# daGloane1_1.net
KiCad netlist of a schematic drawn in EAGLE
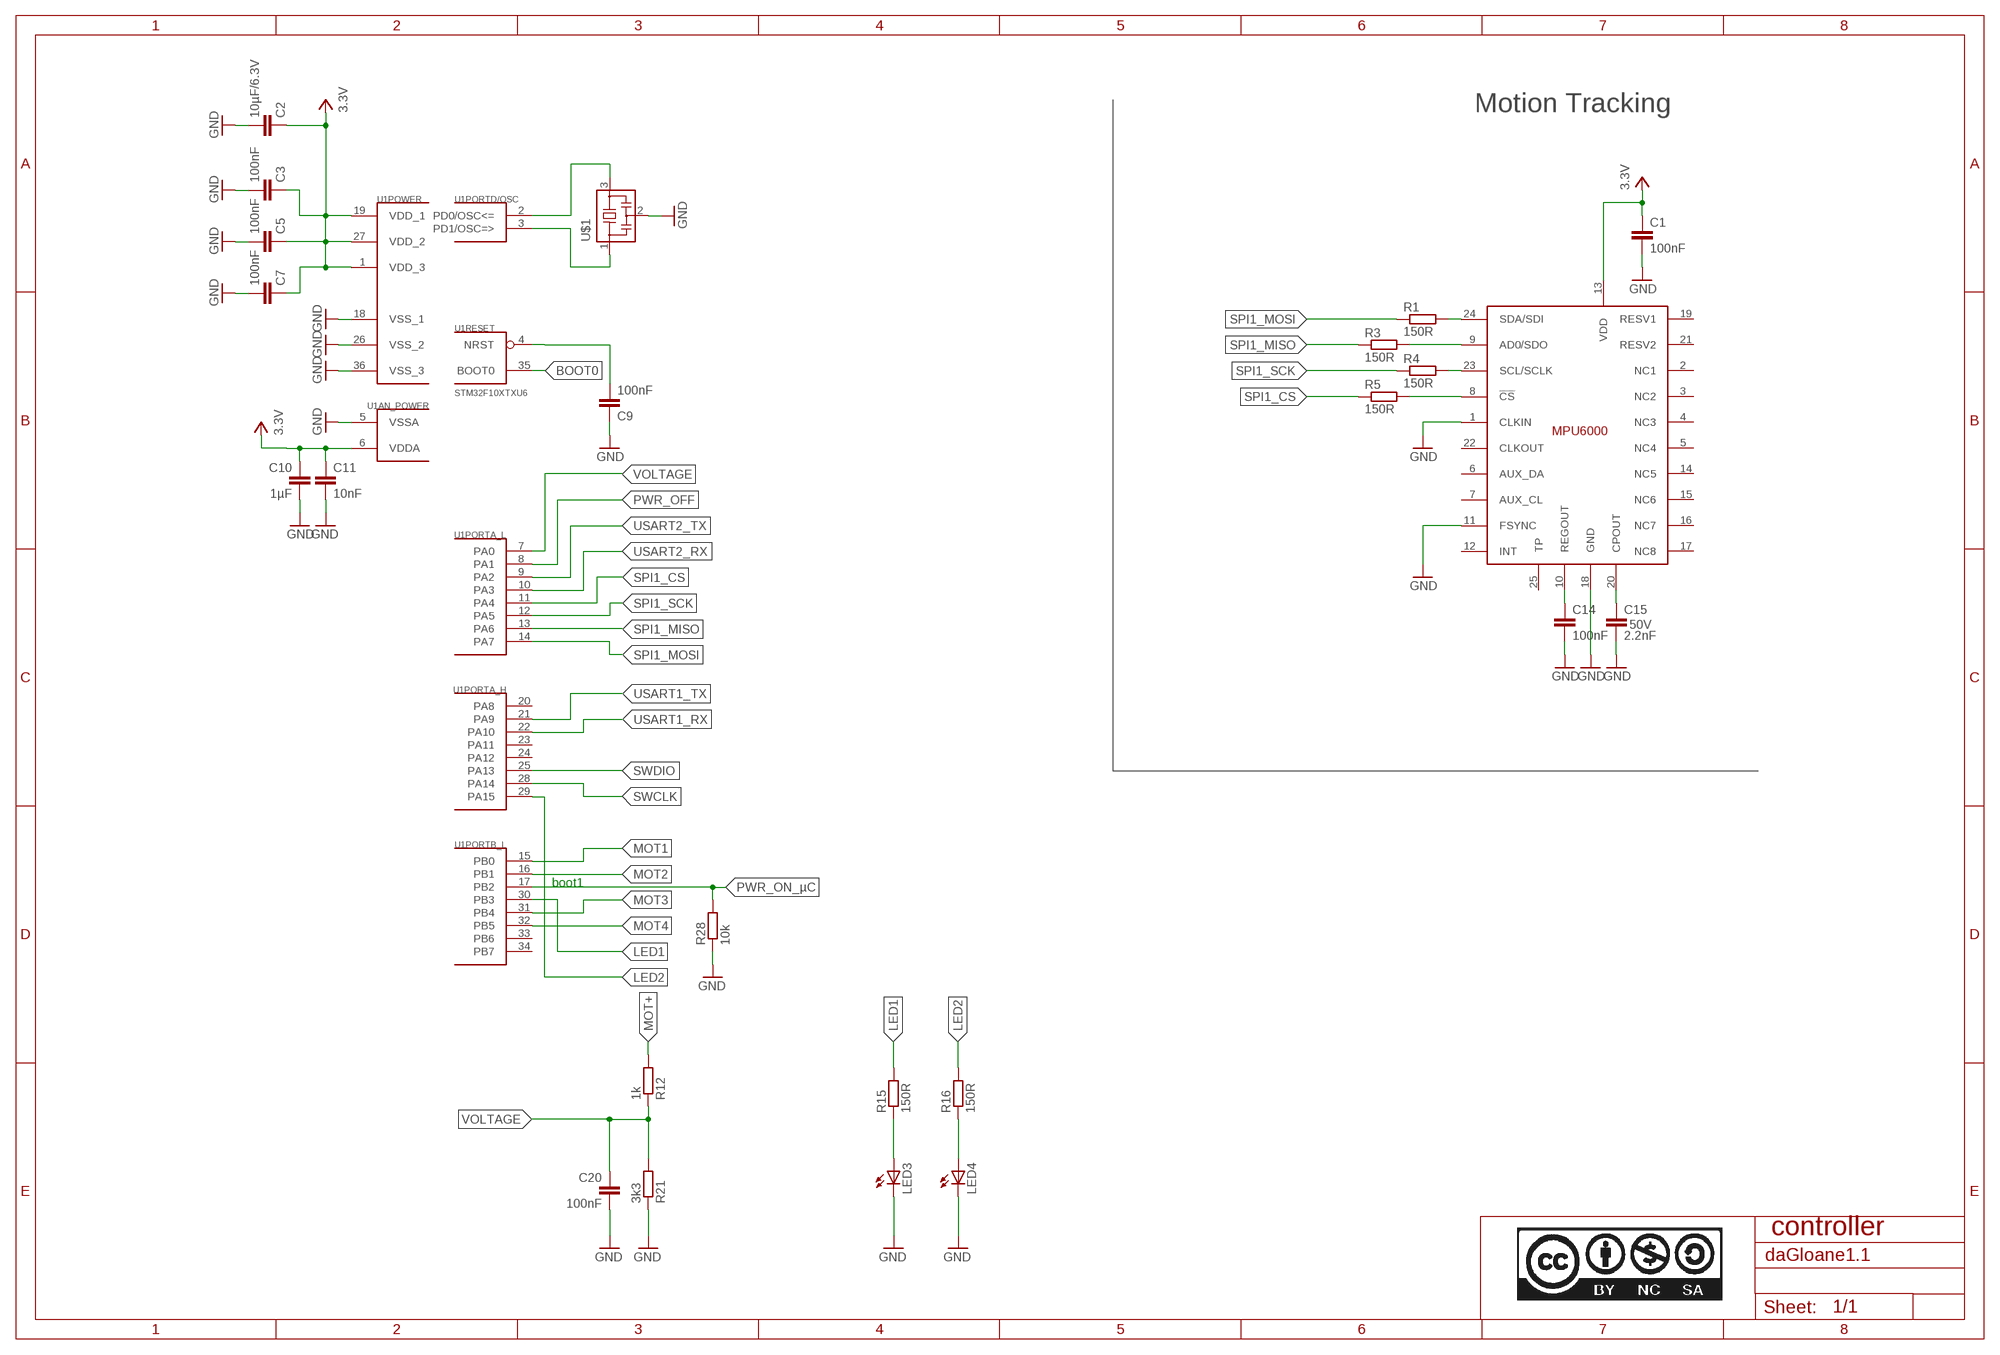
[diagram p0: schematic, sheet 1, part 1 of 3]
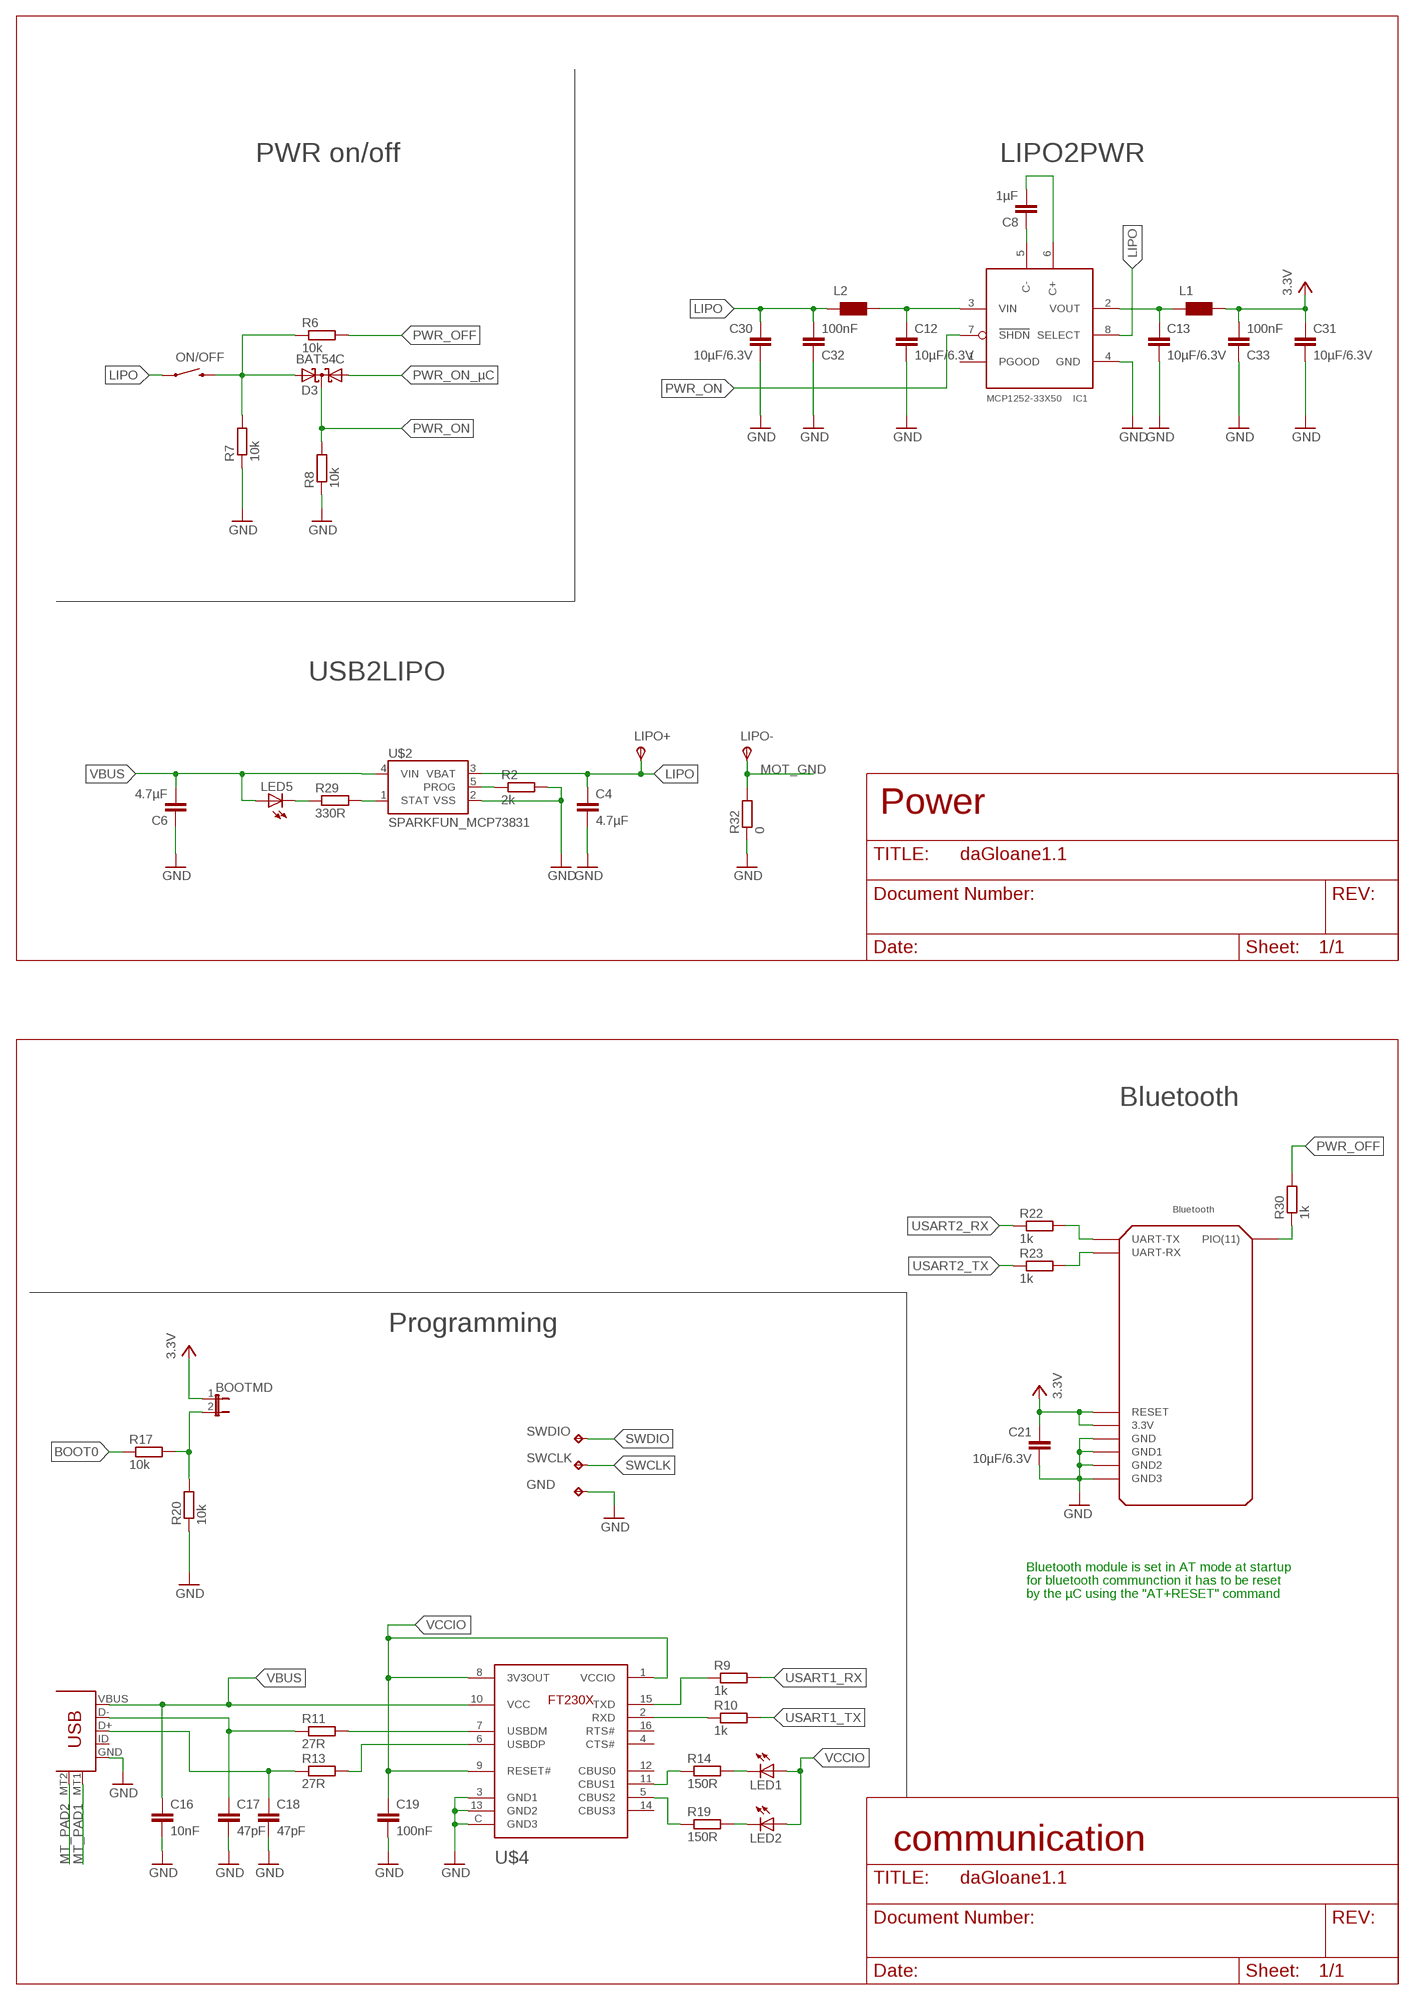
[diagram p1: schematic, sheet 1, part 2 of 3]
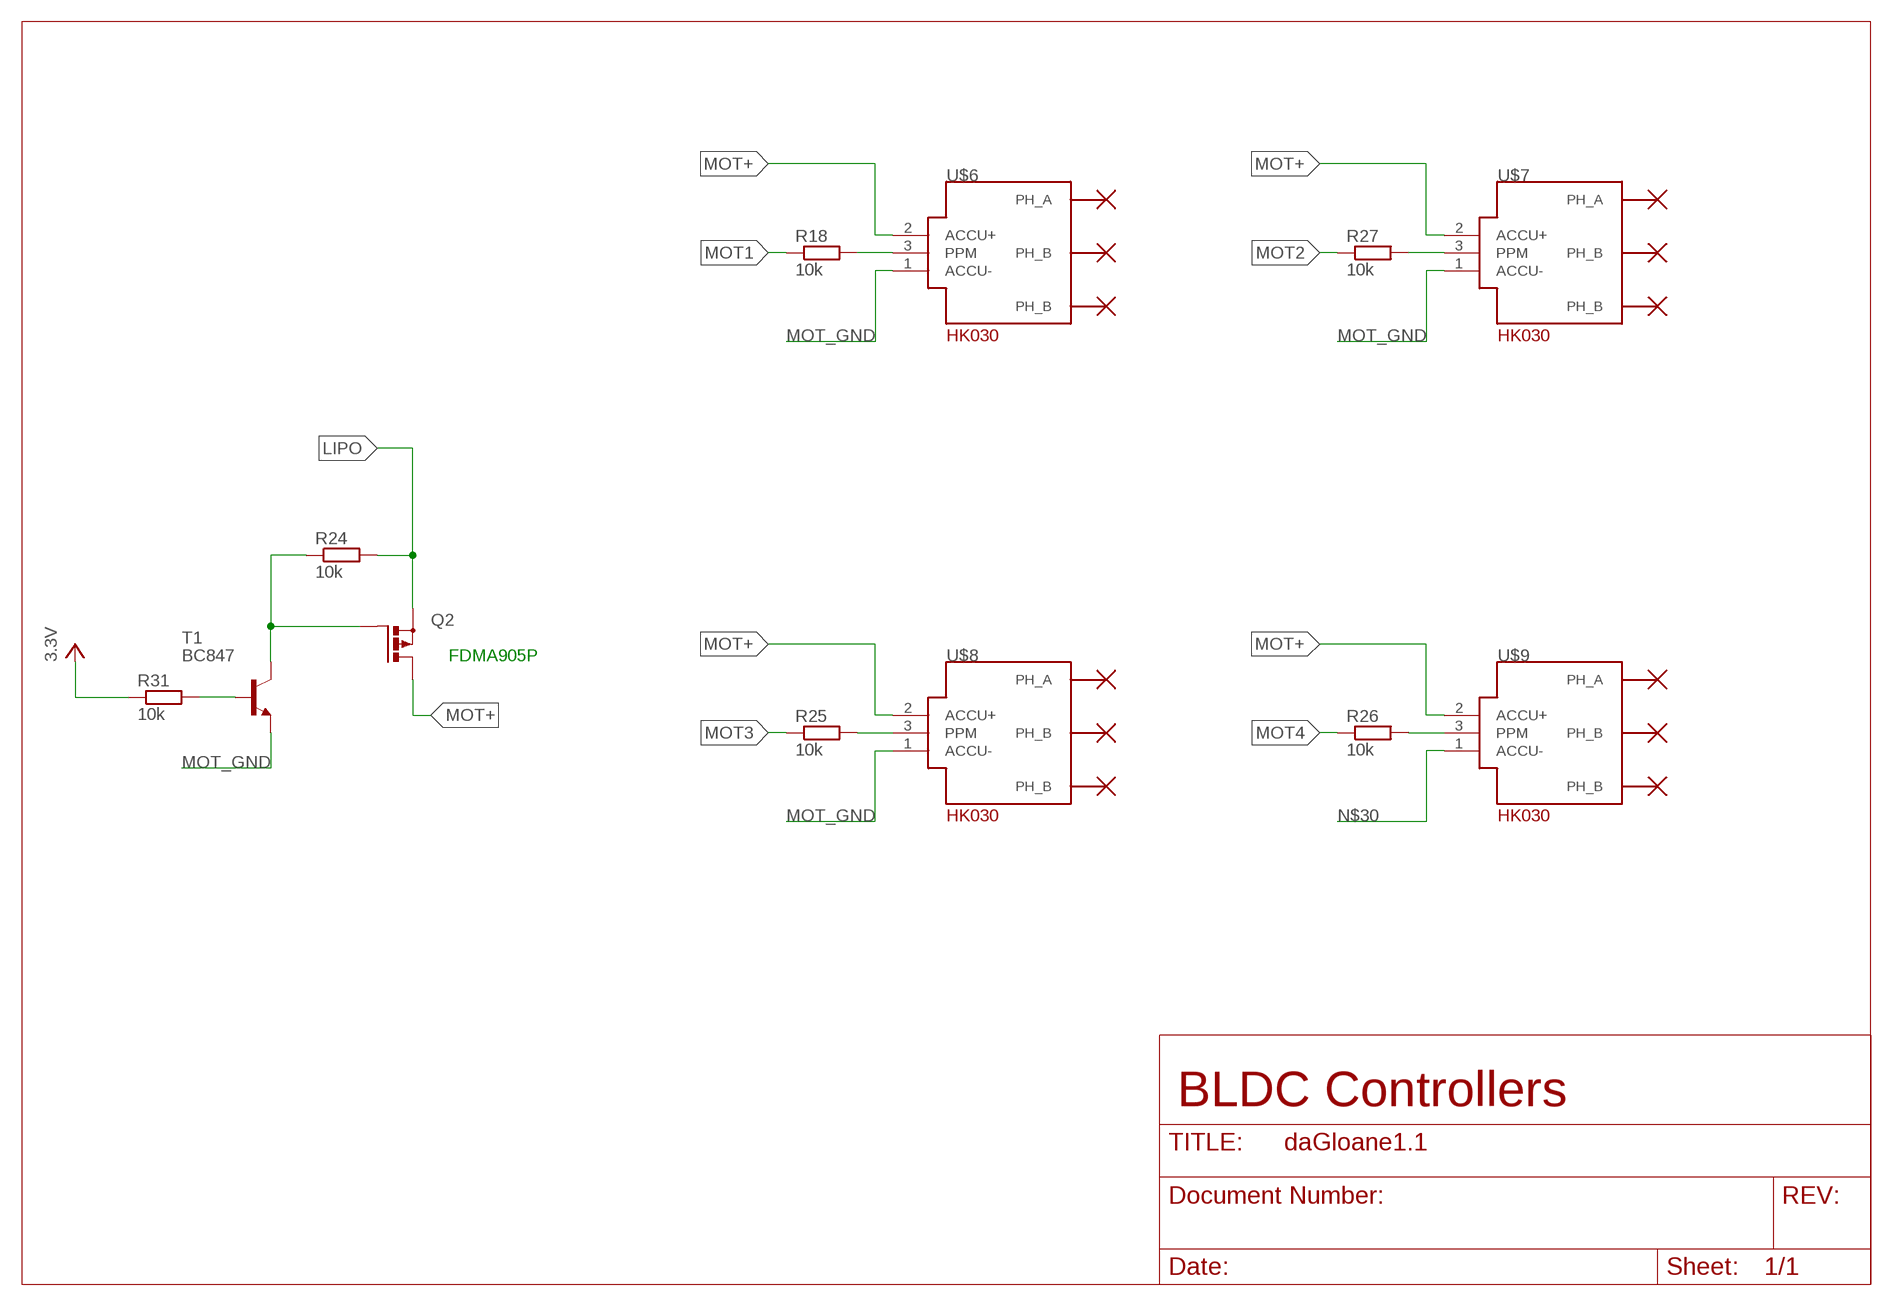
[diagram p2: schematic, sheet 1, part 3 of 3]

(export (version "E")
  (design (tool "Eeschema 10.0.6"))
  (components
    (comp (ref "BOOTMD")
      (value "JUMPER-2")
      (footprint "eagle-import:1X02_50MIL")
      (libsource (lib "eagle-import") (part "JUMPER-2"))
    )
    (comp (ref "C1")
      (value "100nF")
      (footprint "eagle-import:C0603")
      (libsource (lib "eagle-import") (part "C-EUC0603"))
    )
    (comp (ref "C2")
      (value "10µF/6.3V")
      (footprint "eagle-import:C0805")
      (libsource (lib "eagle-import") (part "C-EUC0805"))
    )
    (comp (ref "C3")
      (value "100nF")
      (footprint "eagle-import:C0603")
      (libsource (lib "eagle-import") (part "C-EUC0603"))
    )
    (comp (ref "C4")
      (value "4.7µF")
      (footprint "eagle-import:C0603")
      (libsource (lib "eagle-import") (part "C-EUC0603"))
    )
    (comp (ref "C5")
      (value "100nF")
      (footprint "eagle-import:C0603")
      (libsource (lib "eagle-import") (part "C-EUC0603"))
    )
    (comp (ref "C6")
      (value "4.7µF")
      (footprint "eagle-import:C0603")
      (libsource (lib "eagle-import") (part "C-EUC0603"))
    )
    (comp (ref "C7")
      (value "100nF")
      (footprint "eagle-import:C0603")
      (libsource (lib "eagle-import") (part "C-EUC0603"))
    )
    (comp (ref "C8")
      (value "1µF")
      (footprint "eagle-import:C0603")
      (libsource (lib "eagle-import") (part "C-EUC0603"))
    )
    (comp (ref "C9")
      (value "100nF")
      (footprint "eagle-import:C0603")
      (libsource (lib "eagle-import") (part "C-EUC0603"))
    )
    (comp (ref "C10")
      (value "1µF")
      (footprint "eagle-import:C0603")
      (libsource (lib "eagle-import") (part "C-EUC0603"))
    )
    (comp (ref "C11")
      (value "10nF")
      (footprint "eagle-import:C0603")
      (libsource (lib "eagle-import") (part "C-EUC0603"))
    )
    (comp (ref "C12")
      (value "10µF/6.3V")
      (footprint "eagle-import:C0805")
      (libsource (lib "eagle-import") (part "C-EUC0805"))
    )
    (comp (ref "C13")
      (value "10µF/6.3V")
      (footprint "eagle-import:C0805")
      (libsource (lib "eagle-import") (part "C-EUC0805"))
    )
    (comp (ref "C14")
      (value "100nF")
      (footprint "eagle-import:C0603")
      (libsource (lib "eagle-import") (part "C-EUC0603"))
    )
    (comp (ref "C15")
      (value "2.2nF")
      (footprint "eagle-import:C0603")
      (fields (field (name "VOLTAGE") "50V"))
      (libsource (lib "eagle-import") (part "C-EUC0603"))
    )
    (comp (ref "C16")
      (value "10nF")
      (footprint "eagle-import:C0603")
      (libsource (lib "eagle-import") (part "C-EUC0603"))
    )
    (comp (ref "C17")
      (value "47pF")
      (footprint "eagle-import:C0603")
      (libsource (lib "eagle-import") (part "C-EUC0603"))
    )
    (comp (ref "C18")
      (value "47pF")
      (footprint "eagle-import:C0603")
      (libsource (lib "eagle-import") (part "C-EUC0603"))
    )
    (comp (ref "C19")
      (value "100nF")
      (footprint "eagle-import:C0603")
      (libsource (lib "eagle-import") (part "C-EUC0603"))
    )
    (comp (ref "C20")
      (value "100nF")
      (footprint "eagle-import:C0603")
      (libsource (lib "eagle-import") (part "C-EUC0603"))
    )
    (comp (ref "C21")
      (value "10µF/6.3V")
      (footprint "eagle-import:C0805")
      (libsource (lib "eagle-import") (part "C-EUC0805"))
    )
    (comp (ref "C30")
      (value "10µF/6.3V")
      (footprint "eagle-import:C0805")
      (libsource (lib "eagle-import") (part "C-EUC0805"))
    )
    (comp (ref "C31")
      (value "10µF/6.3V")
      (footprint "eagle-import:C0805")
      (libsource (lib "eagle-import") (part "C-EUC0805"))
    )
    (comp (ref "C32")
      (value "100nF")
      (footprint "eagle-import:C0603")
      (libsource (lib "eagle-import") (part "C-EUC0603"))
    )
    (comp (ref "C33")
      (value "100nF")
      (footprint "eagle-import:C0603")
      (libsource (lib "eagle-import") (part "C-EUC0603"))
    )
    (comp (ref "D3")
      (value "BAT54C")
      (footprint "eagle-import:SOT23")
      (libsource (lib "eagle-import") (part "BAT54C"))
    )
    (comp (ref "GND")
      (value "TESTPAD_TPB1,27")
      (footprint "eagle-import:TESTPAD_B1,27")
      (libsource (lib "eagle-import") (part "TESTPAD_TPB1,27"))
    )
    (comp (ref "IC1")
      (value "MCP1252-33X50")
      (footprint "eagle-import:MSOP8")
      (libsource (lib "eagle-import") (part "MCP1252-33X50"))
    )
    (comp (ref "L1")
      (value "WUERTH-ELEKTRONIK_WE-KI_0805_B")
      (footprint "eagle-import:WUERTH-ELEKTRONIK_WE-KI_0805_B")
      (libsource (lib "eagle-import") (part "WUERTH-ELEKTRONIK_WE-KI_0805_B"))
    )
    (comp (ref "L2")
      (value "WUERTH-ELEKTRONIK_WE-KI_0805_B")
      (footprint "eagle-import:WUERTH-ELEKTRONIK_WE-KI_0805_B")
      (libsource (lib "eagle-import") (part "WUERTH-ELEKTRONIK_WE-KI_0805_B"))
    )
    (comp (ref "LED1")
      (value "LEDCHIPLED_0603")
      (footprint "eagle-import:CHIPLED_0603")
      (libsource (lib "eagle-import") (part "LEDCHIPLED_0603"))
    )
    (comp (ref "LED2")
      (value "LEDCHIPLED_0603")
      (footprint "eagle-import:CHIPLED_0603")
      (libsource (lib "eagle-import") (part "LEDCHIPLED_0603"))
    )
    (comp (ref "LED3")
      (value "LEDCHIPLED_0603")
      (footprint "eagle-import:CHIPLED_0603")
      (libsource (lib "eagle-import") (part "LEDCHIPLED_0603"))
    )
    (comp (ref "LED4")
      (value "LEDCHIPLED_0603")
      (footprint "eagle-import:CHIPLED_0603")
      (libsource (lib "eagle-import") (part "LEDCHIPLED_0603"))
    )
    (comp (ref "LED5")
      (value "LEDCHIPLED_0603")
      (footprint "eagle-import:CHIPLED_0603")
      (libsource (lib "eagle-import") (part "LEDCHIPLED_0603"))
    )
    (comp (ref "LIPO+")
      (value "TPSPAD1-13")
      (footprint "eagle-import:P1-13")
      (libsource (lib "eagle-import") (part "TPSPAD1-13"))
    )
    (comp (ref "LIPO-")
      (value "TPSPAD1-13")
      (footprint "eagle-import:P1-13")
      (libsource (lib "eagle-import") (part "TPSPAD1-13"))
    )
    (comp (ref "ON/OFF")
      (value "SWITCH-MOMENTARY-2SMD")
      (footprint "eagle-import:TACTILE_SWITCH_SMD")
      (libsource (lib "eagle-import") (part "SWITCH-MOMENTARY-2SMD"))
    )
    (comp (ref "Q2")
      (value "P-MOSFET-SO8")
      (footprint "eagle-import:MICROFET2X2")
      (libsource (lib "eagle-import") (part "P-MOSFET-SO8"))
    )
    (comp (ref "R1")
      (value "150R")
      (footprint "eagle-import:R0603")
      (libsource (lib "eagle-import") (part "R-EU_R0603"))
    )
    (comp (ref "R2")
      (value "2k")
      (footprint "eagle-import:R0603")
      (libsource (lib "eagle-import") (part "R-EU_R0603"))
    )
    (comp (ref "R3")
      (value "150R")
      (footprint "eagle-import:R0603")
      (libsource (lib "eagle-import") (part "R-EU_R0603"))
    )
    (comp (ref "R4")
      (value "150R")
      (footprint "eagle-import:R0603")
      (libsource (lib "eagle-import") (part "R-EU_R0603"))
    )
    (comp (ref "R5")
      (value "150R")
      (footprint "eagle-import:R0603")
      (libsource (lib "eagle-import") (part "R-EU_R0603"))
    )
    (comp (ref "R6")
      (value "10k")
      (footprint "eagle-import:R0603")
      (libsource (lib "eagle-import") (part "R-EU_R0603"))
    )
    (comp (ref "R7")
      (value "10k")
      (footprint "eagle-import:R0603")
      (libsource (lib "eagle-import") (part "R-EU_R0603"))
    )
    (comp (ref "R8")
      (value "10k")
      (footprint "eagle-import:R0603")
      (libsource (lib "eagle-import") (part "R-EU_R0603"))
    )
    (comp (ref "R9")
      (value "1k")
      (footprint "eagle-import:R0603")
      (libsource (lib "eagle-import") (part "R-EU_R0603"))
    )
    (comp (ref "R10")
      (value "1k")
      (footprint "eagle-import:R0603")
      (libsource (lib "eagle-import") (part "R-EU_R0603"))
    )
    (comp (ref "R11")
      (value "27R")
      (footprint "eagle-import:R0603")
      (libsource (lib "eagle-import") (part "R-EU_R0603"))
    )
    (comp (ref "R12")
      (value "1k")
      (footprint "eagle-import:R0603")
      (libsource (lib "eagle-import") (part "R-EU_R0603"))
    )
    (comp (ref "R13")
      (value "27R")
      (footprint "eagle-import:R0603")
      (libsource (lib "eagle-import") (part "R-EU_R0603"))
    )
    (comp (ref "R14")
      (value "150R")
      (footprint "eagle-import:R0603")
      (libsource (lib "eagle-import") (part "R-EU_R0603"))
    )
    (comp (ref "R15")
      (value "150R")
      (footprint "eagle-import:R0603")
      (libsource (lib "eagle-import") (part "R-EU_R0603"))
    )
    (comp (ref "R16")
      (value "150R")
      (footprint "eagle-import:R0603")
      (libsource (lib "eagle-import") (part "R-EU_R0603"))
    )
    (comp (ref "R17")
      (value "10k")
      (footprint "eagle-import:R0603")
      (libsource (lib "eagle-import") (part "R-EU_R0603"))
    )
    (comp (ref "R18")
      (value "10k")
      (footprint "eagle-import:R0603")
      (libsource (lib "eagle-import") (part "R-EU_R0603"))
    )
    (comp (ref "R19")
      (value "150R")
      (footprint "eagle-import:R0603")
      (libsource (lib "eagle-import") (part "R-EU_R0603"))
    )
    (comp (ref "R20")
      (value "10k")
      (footprint "eagle-import:R0603")
      (libsource (lib "eagle-import") (part "R-EU_R0603"))
    )
    (comp (ref "R21")
      (value "3k3")
      (footprint "eagle-import:R0603")
      (libsource (lib "eagle-import") (part "R-EU_R0603"))
    )
    (comp (ref "R22")
      (value "1k")
      (footprint "eagle-import:R0603")
      (libsource (lib "eagle-import") (part "R-EU_R0603"))
    )
    (comp (ref "R23")
      (value "1k")
      (footprint "eagle-import:R0603")
      (libsource (lib "eagle-import") (part "R-EU_R0603"))
    )
    (comp (ref "R24")
      (value "10k")
      (footprint "eagle-import:R0603")
      (libsource (lib "eagle-import") (part "R-EU_R0603"))
    )
    (comp (ref "R25")
      (value "10k")
      (footprint "eagle-import:R0603")
      (libsource (lib "eagle-import") (part "R-EU_R0603"))
    )
    (comp (ref "R26")
      (value "10k")
      (footprint "eagle-import:R0603")
      (libsource (lib "eagle-import") (part "R-EU_R0603"))
    )
    (comp (ref "R27")
      (value "10k")
      (footprint "eagle-import:R0603")
      (libsource (lib "eagle-import") (part "R-EU_R0603"))
    )
    (comp (ref "R28")
      (value "10k")
      (footprint "eagle-import:R0603")
      (libsource (lib "eagle-import") (part "R-EU_R0603"))
    )
    (comp (ref "R29")
      (value "330R")
      (footprint "eagle-import:R0603")
      (libsource (lib "eagle-import") (part "R-EU_R0603"))
    )
    (comp (ref "R30")
      (value "1k")
      (footprint "eagle-import:R0603")
      (libsource (lib "eagle-import") (part "R-EU_R0603"))
    )
    (comp (ref "R31")
      (value "10k")
      (footprint "eagle-import:R0603")
      (libsource (lib "eagle-import") (part "R-EU_R0603"))
    )
    (comp (ref "R32")
      (value "0")
      (footprint "eagle-import:R0603")
      (libsource (lib "eagle-import") (part "R-EU_R0603"))
    )
    (comp (ref "SWCLK")
      (value "TESTPAD_TPB1,27")
      (footprint "eagle-import:TESTPAD_B1,27")
      (libsource (lib "eagle-import") (part "TESTPAD_TPB1,27"))
    )
    (comp (ref "SWDIO")
      (value "TESTPAD_TPB1,27")
      (footprint "eagle-import:TESTPAD_B1,27")
      (libsource (lib "eagle-import") (part "TESTPAD_TPB1,27"))
    )
    (comp (ref "T1")
      (value "BC847")
      (footprint "eagle-import:SOT23")
      (libsource (lib "eagle-import") (part "BC847"))
    )
    (comp (ref "U$1")
      (value "MURATA-FILTER_CSTCE__G")
      (footprint "eagle-import:MURATA-FILTER_CSTCE__G")
      (libsource (lib "eagle-import") (part "MURATA-FILTER_CSTCE__G"))
    )
    (comp (ref "U$2")
      (value "SPARKFUN_MCP73831")
      (footprint "eagle-import:SPARKFUN_SOT23-5")
      (libsource (lib "eagle-import") (part "SPARKFUN_MCP73831"))
    )
    (comp (ref "U$3")
      (value "MPU6000")
      (footprint "eagle-import:MPU6000")
      (libsource (lib "eagle-import") (part "MPU6000"))
    )
    (comp (ref "U$4")
      (value "SERIAL_FT230XQ")
      (footprint "eagle-import:SERIAL_QFN4X4-16")
      (libsource (lib "eagle-import") (part "SERIAL_FT230XQ"))
    )
    (comp (ref "U$5")
      (value "BLUETOOTH_REDUCED")
      (footprint "eagle-import:BLUETOOTH_REDUCED")
      (libsource (lib "eagle-import") (part "BLUETOOTH_REDUCED"))
    )
    (comp (ref "U$6")
      (value "3A_BLDC_CONTROLLER")
      (footprint "eagle-import:3A_BLDC_CONTROLLER")
      (libsource (lib "eagle-import") (part "3A_BLDC_CONTROLLER"))
    )
    (comp (ref "U$7")
      (value "3A_BLDC_CONTROLLER")
      (footprint "eagle-import:3A_BLDC_CONTROLLER")
      (libsource (lib "eagle-import") (part "3A_BLDC_CONTROLLER"))
    )
    (comp (ref "U$8")
      (value "3A_BLDC_CONTROLLER")
      (footprint "eagle-import:3A_BLDC_CONTROLLER")
      (libsource (lib "eagle-import") (part "3A_BLDC_CONTROLLER"))
    )
    (comp (ref "U$9")
      (value "3A_BLDC_CONTROLLER")
      (footprint "eagle-import:3A_BLDC_CONTROLLER")
      (libsource (lib "eagle-import") (part "3A_BLDC_CONTROLLER"))
    )
    (comp (ref "U1")
      (value "STM32F10XTXU6")
      (footprint "eagle-import:VFQFPN36")
      (libsource (lib "eagle-import") (part "STM32F10XTXU6"))
    )
    (comp (ref "X2")
      (value "USB_MICROB_PLUG_MT")
      (footprint "eagle-import:SPARKFUN-CONNECTORS_USB-MICROB")
      (libsource (lib "eagle-import") (part "USB_MICROB_PLUG_MT"))
    )
  )
  (nets
    (net (code "1") (name "/MOT_GND") (class "Default")
      (node (ref "LIPO-") (pin "TP") (pinfunction "PP_TP") (pintype "input"))
      (node (ref "R32") (pin "2") (pinfunction "2_2") (pintype "passive"))
      (node (ref "T1") (pin "2") (pinfunction "E_2") (pintype "passive"))
      (node (ref "U$6") (pin "1") (pinfunction "ACCU-_1") (pintype "power_in"))
      (node (ref "U$7") (pin "1") (pinfunction "ACCU-_1") (pintype "power_in"))
      (node (ref "U$8") (pin "1") (pinfunction "ACCU-_1") (pintype "power_in"))
    )
    (net (code "4") (name "/MT_PAD1") (class "Default")
      (node (ref "X2") (pin "MT1") (pinfunction "MTN1_MT1") (pintype "no_connect"))
    )
    (net (code "5") (name "/MT_PAD2") (class "Default")
      (node (ref "X2") (pin "MT2") (pinfunction "MTN2_MT2") (pintype "no_connect"))
    )
    (net (code "6") (name "/N$30") (class "Default")
      (node (ref "U$9") (pin "1") (pinfunction "ACCU-_1") (pintype "power_in"))
    )
    (net (code "7") (name "3.3V") (class "Default")
      (node (ref "BOOTMD") (pin "1") (pinfunction "1_1") (pintype "passive"))
      (node (ref "C1") (pin "1") (pinfunction "1_1") (pintype "passive"))
      (node (ref "C10") (pin "1") (pinfunction "1_1") (pintype "passive"))
      (node (ref "C11") (pin "1") (pinfunction "1_1") (pintype "passive"))
      (node (ref "C2") (pin "1") (pinfunction "1_1") (pintype "passive"))
      (node (ref "C21") (pin "1") (pinfunction "1_1") (pintype "passive"))
      (node (ref "C3") (pin "1") (pinfunction "1_1") (pintype "passive"))
      (node (ref "C31") (pin "1") (pinfunction "1_1") (pintype "passive"))
      (node (ref "C33") (pin "2") (pinfunction "2_2") (pintype "passive"))
      (node (ref "C5") (pin "1") (pinfunction "1_1") (pintype "passive"))
      (node (ref "C7") (pin "1") (pinfunction "1_1") (pintype "passive"))
      (node (ref "L1") (pin "1") (pinfunction "2_1") (pintype "passive"))
      (node (ref "R31") (pin "1") (pinfunction "1_1") (pintype "passive"))
      (node (ref "U$3") (pin "13") (pinfunction "VDD_13") (pintype "power_in"))
      (node (ref "U$5") (pin "P$11") (pinfunction "RESET_P$11") (pintype "input"))
      (node (ref "U$5") (pin "P$12") (pinfunction "3.3V_P$12") (pintype "power_in"))
      (node (ref "U1") (pin "1") (pinfunction "VDD_3_1") (pintype "power_in"))
      (node (ref "U1") (pin "19") (pinfunction "VDD_1_19") (pintype "power_in"))
      (node (ref "U1") (pin "27") (pinfunction "VDD_2_27") (pintype "power_in"))
      (node (ref "U1") (pin "6") (pinfunction "VDDA_6") (pintype "power_in"))
    )
    (net (code "8") (name "BOOT0") (class "Default")
      (node (ref "R17") (pin "1") (pinfunction "1_1") (pintype "passive"))
      (node (ref "U1") (pin "35") (pinfunction "BOOT0_35") (pintype "input"))
    )
    (net (code "9") (name "GND") (class "Default")
      (node (ref "C1") (pin "2") (pinfunction "2_2") (pintype "passive"))
      (node (ref "C10") (pin "2") (pinfunction "2_2") (pintype "passive"))
      (node (ref "C11") (pin "2") (pinfunction "2_2") (pintype "passive"))
      (node (ref "C12") (pin "2") (pinfunction "2_2") (pintype "passive"))
      (node (ref "C13") (pin "2") (pinfunction "2_2") (pintype "passive"))
      (node (ref "C14") (pin "2") (pinfunction "2_2") (pintype "passive"))
      (node (ref "C15") (pin "2") (pinfunction "2_2") (pintype "passive"))
      (node (ref "C16") (pin "2") (pinfunction "2_2") (pintype "passive"))
      (node (ref "C17") (pin "2") (pinfunction "2_2") (pintype "passive"))
      (node (ref "C18") (pin "2") (pinfunction "2_2") (pintype "passive"))
      (node (ref "C19") (pin "2") (pinfunction "2_2") (pintype "passive"))
      (node (ref "C2") (pin "2") (pinfunction "2_2") (pintype "passive"))
      (node (ref "C20") (pin "2") (pinfunction "2_2") (pintype "passive"))
      (node (ref "C21") (pin "2") (pinfunction "2_2") (pintype "passive"))
      (node (ref "C3") (pin "2") (pinfunction "2_2") (pintype "passive"))
      (node (ref "C30") (pin "2") (pinfunction "2_2") (pintype "passive"))
      (node (ref "C31") (pin "2") (pinfunction "2_2") (pintype "passive"))
      (node (ref "C32") (pin "1") (pinfunction "1_1") (pintype "passive"))
      (node (ref "C33") (pin "1") (pinfunction "1_1") (pintype "passive"))
      (node (ref "C4") (pin "2") (pinfunction "2_2") (pintype "passive"))
      (node (ref "C5") (pin "2") (pinfunction "2_2") (pintype "passive"))
      (node (ref "C6") (pin "1") (pinfunction "1_1") (pintype "passive"))
      (node (ref "C7") (pin "2") (pinfunction "2_2") (pintype "passive"))
      (node (ref "C9") (pin "1") (pinfunction "1_1") (pintype "passive"))
      (node (ref "GND") (pin "PP") (pinfunction "TP_PP") (pintype "input"))
      (node (ref "IC1") (pin "4") (pinfunction "GND_4") (pintype "power_in"))
      (node (ref "LED3") (pin "C") (pinfunction "C_C") (pintype "passive"))
      (node (ref "LED4") (pin "C") (pinfunction "C_C") (pintype "passive"))
      (node (ref "R2") (pin "2") (pinfunction "2_2") (pintype "passive"))
      (node (ref "R20") (pin "1") (pinfunction "1_1") (pintype "passive"))
      (node (ref "R21") (pin "1") (pinfunction "1_1") (pintype "passive"))
      (node (ref "R28") (pin "1") (pinfunction "1_1") (pintype "passive"))
      (node (ref "R32") (pin "1") (pinfunction "1_1") (pintype "passive"))
      (node (ref "R7") (pin "1") (pinfunction "1_1") (pintype "passive"))
      (node (ref "R8") (pin "1") (pinfunction "1_1") (pintype "passive"))
      (node (ref "U$1") (pin "2") (pinfunction "2_2") (pintype "passive"))
      (node (ref "U$2") (pin "2") (pinfunction "VSS_2") (pintype "power_in"))
      (node (ref "U$3") (pin "1") (pinfunction "CLKIN_1") (pintype "input"))
      (node (ref "U$3") (pin "11") (pinfunction "FSYNC_11") (pintype "input"))
      (node (ref "U$3") (pin "18") (pinfunction "GND_18") (pintype "power_in"))
      (node (ref "U$4") (pin "13") (pinfunction "GND2_13") (pintype "power_in"))
      (node (ref "U$4") (pin "3") (pinfunction "GND1_3") (pintype "power_in"))
      (node (ref "U$4") (pin "C") (pinfunction "GND3_C") (pintype "power_in"))
      (node (ref "U$5") (pin "P$13") (pinfunction "GND_P$13") (pintype "power_in"))
      (node (ref "U$5") (pin "P$14") (pinfunction "GND1_P$14") (pintype "power_in"))
      (node (ref "U$5") (pin "P$21") (pinfunction "GND2_P$21") (pintype "power_in"))
      (node (ref "U$5") (pin "P$22") (pinfunction "GND3_P$22") (pintype "power_in"))
      (node (ref "U1") (pin "18") (pinfunction "VSS_1_18") (pintype "power_in"))
      (node (ref "U1") (pin "26") (pinfunction "VSS_2_26") (pintype "power_in"))
      (node (ref "U1") (pin "36") (pinfunction "VSS_3_36") (pintype "power_in"))
      (node (ref "U1") (pin "5") (pinfunction "VSSA_5") (pintype "power_in"))
      (node (ref "X2") (pin "GND") (pinfunction "GND_GND") (pintype "bidirectional"))
    )
    (net (code "10") (name "LED1") (class "Default")
      (node (ref "R15") (pin "2") (pinfunction "2_2") (pintype "passive"))
      (node (ref "U1") (pin "30") (pinfunction "PB3_30") (pintype "bidirectional"))
    )
    (net (code "11") (name "LED2") (class "Default")
      (node (ref "R16") (pin "2") (pinfunction "2_2") (pintype "passive"))
      (node (ref "U1") (pin "29") (pinfunction "PA15_29") (pintype "bidirectional"))
    )
    (net (code "12") (name "LIPO") (class "Default")
      (node (ref "C30") (pin "1") (pinfunction "1_1") (pintype "passive"))
      (node (ref "C32") (pin "2") (pinfunction "2_2") (pintype "passive"))
      (node (ref "C4") (pin "1") (pinfunction "1_1") (pintype "passive"))
      (node (ref "IC1") (pin "8") (pinfunction "SELECT_8") (pintype "input"))
      (node (ref "L2") (pin "2") (pinfunction "1_2") (pintype "passive"))
      (node (ref "LIPO+") (pin "TP") (pinfunction "PP_TP") (pintype "input"))
      (node (ref "ON/OFF") (pin "1") (pinfunction "1_1") (pintype "passive"))
      (node (ref "Q2") (pin "P$4") (pinfunction "S_P$4") (pintype "passive"))
      (node (ref "Q2") (pin "P$7") (pinfunction "S_P$7") (pintype "passive"))
      (node (ref "R24") (pin "2") (pinfunction "2_2") (pintype "passive"))
      (node (ref "U$2") (pin "3") (pinfunction "VBAT_3") (pintype "power_in"))
    )
    (net (code "13") (name "MOT+") (class "Default")
      (node (ref "Q2") (pin "P$1") (pinfunction "D_P$1") (pintype "passive"))
      (node (ref "Q2") (pin "P$2") (pinfunction "D_P$2") (pintype "passive"))
      (node (ref "Q2") (pin "P$5") (pinfunction "D_P$5") (pintype "passive"))
      (node (ref "Q2") (pin "P$6") (pinfunction "D_P$6") (pintype "passive"))
      (node (ref "Q2") (pin "P$8") (pinfunction "D_P$8") (pintype "passive"))
      (node (ref "R12") (pin "2") (pinfunction "2_2") (pintype "passive"))
      (node (ref "U$6") (pin "2") (pinfunction "ACCU+_2") (pintype "power_in"))
      (node (ref "U$7") (pin "2") (pinfunction "ACCU+_2") (pintype "power_in"))
      (node (ref "U$8") (pin "2") (pinfunction "ACCU+_2") (pintype "power_in"))
      (node (ref "U$9") (pin "2") (pinfunction "ACCU+_2") (pintype "power_in"))
    )
    (net (code "14") (name "MOT1") (class "Default")
      (node (ref "R18") (pin "1") (pinfunction "1_1") (pintype "passive"))
      (node (ref "U1") (pin "15") (pinfunction "PB0_15") (pintype "bidirectional"))
    )
    (net (code "15") (name "MOT2") (class "Default")
      (node (ref "R27") (pin "1") (pinfunction "1_1") (pintype "passive"))
      (node (ref "U1") (pin "16") (pinfunction "PB1_16") (pintype "bidirectional"))
    )
    (net (code "16") (name "MOT3") (class "Default")
      (node (ref "R25") (pin "1") (pinfunction "1_1") (pintype "passive"))
      (node (ref "U1") (pin "31") (pinfunction "PB4_31") (pintype "bidirectional"))
    )
    (net (code "17") (name "MOT4") (class "Default")
      (node (ref "R26") (pin "1") (pinfunction "1_1") (pintype "passive"))
      (node (ref "U1") (pin "32") (pinfunction "PB5_32") (pintype "bidirectional"))
    )
    (net (code "18") (name "Net-(BOOTMD-Pad2)") (class "Default")
      (node (ref "BOOTMD") (pin "2") (pinfunction "2_2") (pintype "passive"))
      (node (ref "R17") (pin "2") (pinfunction "2_2") (pintype "passive"))
      (node (ref "R20") (pin "2") (pinfunction "2_2") (pintype "passive"))
    )
    (net (code "19") (name "Net-(C17-Pad1)") (class "Default")
      (node (ref "C17") (pin "1") (pinfunction "1_1") (pintype "passive"))
      (node (ref "R11") (pin "1") (pinfunction "1_1") (pintype "passive"))
      (node (ref "X2") (pin "D-") (pinfunction "D-_D-") (pintype "bidirectional"))
    )
    (net (code "20") (name "Net-(C18-Pad1)") (class "Default")
      (node (ref "C18") (pin "1") (pinfunction "1_1") (pintype "passive"))
      (node (ref "R13") (pin "1") (pinfunction "1_1") (pintype "passive"))
      (node (ref "X2") (pin "D+") (pinfunction "D+_D+") (pintype "bidirectional"))
    )
    (net (code "21") (name "Net-(D3-A2)") (class "Default")
      (node (ref "D3") (pin "2") (pinfunction "A2_2") (pintype "passive"))
      (node (ref "ON/OFF") (pin "3") (pinfunction "2_3") (pintype "passive"))
      (node (ref "R6") (pin "1") (pinfunction "1_1") (pintype "passive"))
      (node (ref "R7") (pin "2") (pinfunction "2_2") (pintype "passive"))
    )
    (net (code "22") (name "Net-(IC1-C+)") (class "Default")
      (node (ref "C8") (pin "2") (pinfunction "2_2") (pintype "passive"))
      (node (ref "IC1") (pin "6") (pinfunction "C+_6") (pintype "passive"))
    )
    (net (code "23") (name "Net-(IC1-C-)") (class "Default")
      (node (ref "C8") (pin "1") (pinfunction "1_1") (pintype "passive"))
      (node (ref "IC1") (pin "5") (pinfunction "C-_5") (pintype "passive"))
    )
    (net (code "24") (name "Net-(IC1-VIN)") (class "Default")
      (node (ref "C12") (pin "1") (pinfunction "1_1") (pintype "passive"))
      (node (ref "IC1") (pin "3") (pinfunction "VIN_3") (pintype "power_in"))
      (node (ref "L2") (pin "1") (pinfunction "2_1") (pintype "passive"))
    )
    (net (code "25") (name "Net-(IC1-VOUT)") (class "Default")
      (node (ref "C13") (pin "1") (pinfunction "1_1") (pintype "passive"))
      (node (ref "IC1") (pin "2") (pinfunction "VOUT_2") (pintype "output"))
      (node (ref "L1") (pin "2") (pinfunction "1_2") (pintype "passive"))
    )
    (net (code "26") (name "Net-(LED1-PadC)") (class "Default")
      (node (ref "LED1") (pin "C") (pinfunction "C_C") (pintype "passive"))
      (node (ref "R14") (pin "2") (pinfunction "2_2") (pintype "passive"))
    )
    (net (code "27") (name "Net-(LED2-PadC)") (class "Default")
      (node (ref "LED2") (pin "C") (pinfunction "C_C") (pintype "passive"))
      (node (ref "R19") (pin "2") (pinfunction "2_2") (pintype "passive"))
    )
    (net (code "28") (name "Net-(LED3-PadA)") (class "Default")
      (node (ref "LED3") (pin "A") (pinfunction "A_A") (pintype "passive"))
      (node (ref "R15") (pin "1") (pinfunction "1_1") (pintype "passive"))
    )
    (net (code "29") (name "Net-(LED4-PadA)") (class "Default")
      (node (ref "LED4") (pin "A") (pinfunction "A_A") (pintype "passive"))
      (node (ref "R16") (pin "1") (pinfunction "1_1") (pintype "passive"))
    )
    (net (code "30") (name "Net-(LED5-PadC)") (class "Default")
      (node (ref "LED5") (pin "C") (pinfunction "C_C") (pintype "passive"))
      (node (ref "R29") (pin "1") (pinfunction "1_1") (pintype "passive"))
    )
    (net (code "31") (name "Net-(Q2-G)") (class "Default")
      (node (ref "Q2") (pin "P$3") (pinfunction "G_P$3") (pintype "passive"))
      (node (ref "R24") (pin "1") (pinfunction "1_1") (pintype "passive"))
      (node (ref "T1") (pin "3") (pinfunction "C_3") (pintype "passive"))
    )
    (net (code "32") (name "Net-(T1-B)") (class "Default")
      (node (ref "R31") (pin "2") (pinfunction "2_2") (pintype "passive"))
      (node (ref "T1") (pin "1") (pinfunction "B_1") (pintype "passive"))
    )
    (net (code "33") (name "Net-(U$2-PROG)") (class "Default")
      (node (ref "R2") (pin "1") (pinfunction "1_1") (pintype "passive"))
      (node (ref "U$2") (pin "5") (pinfunction "PROG_5") (pintype "input"))
    )
    (net (code "34") (name "Net-(U$2-STAT)") (class "Default")
      (node (ref "R29") (pin "2") (pinfunction "2_2") (pintype "passive"))
      (node (ref "U$2") (pin "1") (pinfunction "STAT_1") (pintype "output"))
    )
    (net (code "35") (name "Net-(U$3-AD0{slash}SDO)") (class "Default")
      (node (ref "R3") (pin "2") (pinfunction "2_2") (pintype "passive"))
      (node (ref "U$3") (pin "9") (pinfunction "AD0/SDO_9") (pintype "output"))
    )
    (net (code "36") (name "Net-(U$3-CPOUT)") (class "Default")
      (node (ref "C15") (pin "1") (pinfunction "1_1") (pintype "passive"))
      (node (ref "U$3") (pin "20") (pinfunction "CPOUT_20") (pintype "bidirectional"))
    )
    (net (code "37") (name "Net-(U$3-REGOUT)") (class "Default")
      (node (ref "C14") (pin "1") (pinfunction "1_1") (pintype "passive"))
      (node (ref "U$3") (pin "10") (pinfunction "REGOUT_10") (pintype "bidirectional"))
    )
    (net (code "38") (name "Net-(U$3-SCL{slash}SCLK)") (class "Default")
      (node (ref "R4") (pin "2") (pinfunction "2_2") (pintype "passive"))
      (node (ref "U$3") (pin "23") (pinfunction "SCL/SCLK_23") (pintype "input"))
    )
    (net (code "39") (name "Net-(U$3-SDA{slash}SDI)") (class "Default")
      (node (ref "R1") (pin "2") (pinfunction "2_2") (pintype "passive"))
      (node (ref "U$3") (pin "24") (pinfunction "SDA/SDI_24") (pintype "input"))
    )
    (net (code "40") (name "Net-(U$3-~{CS})") (class "Default")
      (node (ref "R5") (pin "2") (pinfunction "2_2") (pintype "passive"))
      (node (ref "U$3") (pin "8") (pinfunction "~{CS}_8") (pintype "input"))
    )
    (net (code "41") (name "Net-(U$4-CBUS1)") (class "Default")
      (node (ref "R14") (pin "1") (pinfunction "1_1") (pintype "passive"))
      (node (ref "U$4") (pin "11") (pinfunction "CBUS1_11") (pintype "bidirectional"))
    )
    (net (code "42") (name "Net-(U$4-CBUS2)") (class "Default")
      (node (ref "R19") (pin "1") (pinfunction "1_1") (pintype "passive"))
      (node (ref "U$4") (pin "5") (pinfunction "CBUS2_5") (pintype "bidirectional"))
    )
    (net (code "43") (name "Net-(U$4-RXD)") (class "Default")
      (node (ref "R10") (pin "1") (pinfunction "1_1") (pintype "passive"))
      (node (ref "U$4") (pin "2") (pinfunction "RXD_2") (pintype "input"))
    )
    (net (code "44") (name "Net-(U$4-TXD)") (class "Default")
      (node (ref "R9") (pin "1") (pinfunction "1_1") (pintype "passive"))
      (node (ref "U$4") (pin "15") (pinfunction "TXD_15") (pintype "output"))
    )
    (net (code "45") (name "Net-(U$4-USBDM)") (class "Default")
      (node (ref "R11") (pin "2") (pinfunction "2_2") (pintype "passive"))
      (node (ref "U$4") (pin "7") (pinfunction "USBDM_7") (pintype "bidirectional"))
    )
    (net (code "46") (name "Net-(U$4-USBDP)") (class "Default")
      (node (ref "R13") (pin "2") (pinfunction "2_2") (pintype "passive"))
      (node (ref "U$4") (pin "6") (pinfunction "USBDP_6") (pintype "bidirectional"))
    )
    (net (code "47") (name "Net-(U$5-PIO(11))") (class "Default")
      (node (ref "R30") (pin "1") (pinfunction "1_1") (pintype "passive"))
      (node (ref "U$5") (pin "P$34") (pinfunction "PIO(11)_P$34") (pintype "bidirectional"))
    )
    (net (code "48") (name "Net-(U$5-UART-RX)") (class "Default")
      (node (ref "R23") (pin "2") (pinfunction "2_2") (pintype "passive"))
      (node (ref "U$5") (pin "P$2") (pinfunction "UART-RX_P$2") (pintype "input"))
    )
    (net (code "49") (name "Net-(U$5-UART-TX)") (class "Default")
      (node (ref "R22") (pin "2") (pinfunction "2_2") (pintype "passive"))
      (node (ref "U$5") (pin "P$1") (pinfunction "UART-TX_P$1") (pintype "output"))
    )
    (net (code "50") (name "Net-(U$6-PPM)") (class "Default")
      (node (ref "R18") (pin "2") (pinfunction "2_2") (pintype "passive"))
      (node (ref "U$6") (pin "3") (pinfunction "PPM_3") (pintype "input"))
    )
    (net (code "51") (name "Net-(U$7-PPM)") (class "Default")
      (node (ref "R27") (pin "2") (pinfunction "2_2") (pintype "passive"))
      (node (ref "U$7") (pin "3") (pinfunction "PPM_3") (pintype "input"))
    )
    (net (code "52") (name "Net-(U$8-PPM)") (class "Default")
      (node (ref "R25") (pin "2") (pinfunction "2_2") (pintype "passive"))
      (node (ref "U$8") (pin "3") (pinfunction "PPM_3") (pintype "input"))
    )
    (net (code "53") (name "Net-(U$9-PPM)") (class "Default")
      (node (ref "R26") (pin "2") (pinfunction "2_2") (pintype "passive"))
      (node (ref "U$9") (pin "3") (pinfunction "PPM_3") (pintype "input"))
    )
    (net (code "54") (name "Net-(U1E-PD0{slash}OSC<=)") (class "Default")
      (node (ref "U$1") (pin "3") (pinfunction "3_3") (pintype "passive"))
      (node (ref "U1") (pin "2") (pinfunction "PD0/OSC<=_2") (pintype "bidirectional"))
    )
    (net (code "55") (name "Net-(U1E-PD1{slash}OSC=>)") (class "Default")
      (node (ref "U$1") (pin "1") (pinfunction "1_1") (pintype "passive"))
      (node (ref "U1") (pin "3") (pinfunction "PD1/OSC=>_3") (pintype "bidirectional"))
    )
    (net (code "56") (name "Net-(U1G-NRST)") (class "Default")
      (node (ref "C9") (pin "2") (pinfunction "2_2") (pintype "passive"))
      (node (ref "U1") (pin "4") (pinfunction "NRST_4") (pintype "input"))
    )
    (net (code "57") (name "PWR_OFF") (class "Default")
      (node (ref "R30") (pin "2") (pinfunction "2_2") (pintype "passive"))
      (node (ref "R6") (pin "2") (pinfunction "2_2") (pintype "passive"))
      (node (ref "U1") (pin "8") (pinfunction "PA1_8") (pintype "bidirectional"))
    )
    (net (code "58") (name "PWR_ON") (class "Default")
      (node (ref "D3") (pin "3") (pinfunction "CC_3") (pintype "passive"))
      (node (ref "IC1") (pin "7") (pinfunction "SHDN_7") (pintype "input"))
      (node (ref "R8") (pin "2") (pinfunction "2_2") (pintype "passive"))
    )
    (net (code "59") (name "PWR_ON_µC") (class "Default")
      (node (ref "D3") (pin "1") (pinfunction "A1_1") (pintype "passive"))
      (node (ref "R28") (pin "2") (pinfunction "2_2") (pintype "passive"))
      (node (ref "U1") (pin "17") (pinfunction "PB2_17") (pintype "bidirectional"))
    )
    (net (code "60") (name "SPI1_CS") (class "Default")
      (node (ref "R5") (pin "1") (pinfunction "1_1") (pintype "passive"))
      (node (ref "U1") (pin "11") (pinfunction "PA4_11") (pintype "bidirectional"))
    )
    (net (code "61") (name "SPI1_MISO") (class "Default")
      (node (ref "R3") (pin "1") (pinfunction "1_1") (pintype "passive"))
      (node (ref "U1") (pin "13") (pinfunction "PA6_13") (pintype "bidirectional"))
    )
    (net (code "62") (name "SPI1_MOSI") (class "Default")
      (node (ref "R1") (pin "1") (pinfunction "1_1") (pintype "passive"))
      (node (ref "U1") (pin "14") (pinfunction "PA7_14") (pintype "bidirectional"))
    )
    (net (code "63") (name "SPI1_SCK") (class "Default")
      (node (ref "R4") (pin "1") (pinfunction "1_1") (pintype "passive"))
      (node (ref "U1") (pin "12") (pinfunction "PA5_12") (pintype "bidirectional"))
    )
    (net (code "64") (name "SWCLK") (class "Default")
      (node (ref "SWCLK") (pin "PP") (pinfunction "TP_PP") (pintype "input"))
      (node (ref "U1") (pin "28") (pinfunction "PA14_28") (pintype "bidirectional"))
    )
    (net (code "65") (name "SWDIO") (class "Default")
      (node (ref "SWDIO") (pin "PP") (pinfunction "TP_PP") (pintype "input"))
      (node (ref "U1") (pin "25") (pinfunction "PA13_25") (pintype "bidirectional"))
    )
    (net (code "66") (name "USART1_RX") (class "Default")
      (node (ref "R9") (pin "2") (pinfunction "2_2") (pintype "passive"))
      (node (ref "U1") (pin "22") (pinfunction "PA10_22") (pintype "bidirectional"))
    )
    (net (code "67") (name "USART1_TX") (class "Default")
      (node (ref "R10") (pin "2") (pinfunction "2_2") (pintype "passive"))
      (node (ref "U1") (pin "21") (pinfunction "PA9_21") (pintype "bidirectional"))
    )
    (net (code "68") (name "USART2_RX") (class "Default")
      (node (ref "R22") (pin "1") (pinfunction "1_1") (pintype "passive"))
      (node (ref "U1") (pin "10") (pinfunction "PA3_10") (pintype "bidirectional"))
    )
    (net (code "69") (name "USART2_TX") (class "Default")
      (node (ref "R23") (pin "1") (pinfunction "1_1") (pintype "passive"))
      (node (ref "U1") (pin "9") (pinfunction "PA2_9") (pintype "bidirectional"))
    )
    (net (code "70") (name "VBUS") (class "Default")
      (node (ref "C16") (pin "1") (pinfunction "1_1") (pintype "passive"))
      (node (ref "C6") (pin "2") (pinfunction "2_2") (pintype "passive"))
      (node (ref "LED5") (pin "A") (pinfunction "A_A") (pintype "passive"))
      (node (ref "U$2") (pin "4") (pinfunction "VIN_4") (pintype "power_in"))
      (node (ref "U$4") (pin "10") (pinfunction "VCC_10") (pintype "power_in"))
      (node (ref "X2") (pin "VBUS") (pinfunction "VBUS_VBUS") (pintype "bidirectional"))
    )
    (net (code "71") (name "VCCIO") (class "Default")
      (node (ref "C19") (pin "1") (pinfunction "1_1") (pintype "passive"))
      (node (ref "LED1") (pin "A") (pinfunction "A_A") (pintype "passive"))
      (node (ref "LED2") (pin "A") (pinfunction "A_A") (pintype "passive"))
      (node (ref "U$4") (pin "1") (pinfunction "VCCIO_1") (pintype "input"))
      (node (ref "U$4") (pin "8") (pinfunction "3V3OUT_8") (pintype "output"))
      (node (ref "U$4") (pin "9") (pinfunction "RESET#_9") (pintype "input"))
    )
    (net (code "72") (name "VOLTAGE") (class "Default")
      (node (ref "C20") (pin "1") (pinfunction "1_1") (pintype "passive"))
      (node (ref "R12") (pin "1") (pinfunction "1_1") (pintype "passive"))
      (node (ref "R21") (pin "2") (pinfunction "2_2") (pintype "passive"))
      (node (ref "U1") (pin "7") (pinfunction "PA0_7") (pintype "bidirectional"))
    )
    (net (code "73") (name "unconnected-(IC1-PGOOD-Pad1)") (class "Default")
      (node (ref "IC1") (pin "1") (pinfunction "PGOOD_1") (pintype "output"))
    )
    (net (code "74") (name "unconnected-(U$3-AUX_CL-Pad7)") (class "Default")
      (node (ref "U$3") (pin "7") (pinfunction "AUX_CL_7") (pintype "output"))
    )
    (net (code "75") (name "unconnected-(U$3-AUX_DA-Pad6)") (class "Default")
      (node (ref "U$3") (pin "6") (pinfunction "AUX_DA_6") (pintype "bidirectional"))
    )
    (net (code "76") (name "unconnected-(U$3-CLKOUT-Pad22)") (class "Default")
      (node (ref "U$3") (pin "22") (pinfunction "CLKOUT_22") (pintype "output"))
    )
    (net (code "77") (name "unconnected-(U$3-INT-Pad12)") (class "Default")
      (node (ref "U$3") (pin "12") (pinfunction "INT_12") (pintype "output"))
    )
    (net (code "78") (name "unconnected-(U$3-NC1-Pad2)") (class "Default")
      (node (ref "U$3") (pin "2") (pinfunction "NC1_2") (pintype "no_connect"))
    )
    (net (code "79") (name "unconnected-(U$3-NC2-Pad3)") (class "Default")
      (node (ref "U$3") (pin "3") (pinfunction "NC2_3") (pintype "no_connect"))
    )
    (net (code "80") (name "unconnected-(U$3-NC3-Pad4)") (class "Default")
      (node (ref "U$3") (pin "4") (pinfunction "NC3_4") (pintype "no_connect"))
    )
    (net (code "81") (name "unconnected-(U$3-NC4-Pad5)") (class "Default")
      (node (ref "U$3") (pin "5") (pinfunction "NC4_5") (pintype "no_connect"))
    )
    (net (code "82") (name "unconnected-(U$3-NC5-Pad14)") (class "Default")
      (node (ref "U$3") (pin "14") (pinfunction "NC5_14") (pintype "no_connect"))
    )
    (net (code "83") (name "unconnected-(U$3-NC6-Pad15)") (class "Default")
      (node (ref "U$3") (pin "15") (pinfunction "NC6_15") (pintype "no_connect"))
    )
    (net (code "84") (name "unconnected-(U$3-NC7-Pad16)") (class "Default")
      (node (ref "U$3") (pin "16") (pinfunction "NC7_16") (pintype "no_connect"))
    )
    (net (code "85") (name "unconnected-(U$3-NC8-Pad17)") (class "Default")
      (node (ref "U$3") (pin "17") (pinfunction "NC8_17") (pintype "no_connect"))
    )
    (net (code "86") (name "unconnected-(U$3-RESV1-Pad19)") (class "Default")
      (node (ref "U$3") (pin "19") (pinfunction "RESV1_19") (pintype "no_connect"))
    )
    (net (code "87") (name "unconnected-(U$3-RESV2-Pad21)") (class "Default")
      (node (ref "U$3") (pin "21") (pinfunction "RESV2_21") (pintype "no_connect"))
    )
    (net (code "88") (name "unconnected-(U$3-TP-Pad25)") (class "Default")
      (node (ref "U$3") (pin "25") (pinfunction "TP_25") (pintype "bidirectional"))
    )
    (net (code "89") (name "unconnected-(U$4-CBUS0-Pad12)") (class "Default")
      (node (ref "U$4") (pin "12") (pinfunction "CBUS0_12") (pintype "bidirectional"))
    )
    (net (code "90") (name "unconnected-(U$4-CBUS3-Pad14)") (class "Default")
      (node (ref "U$4") (pin "14") (pinfunction "CBUS3_14") (pintype "bidirectional"))
    )
    (net (code "91") (name "unconnected-(U$4-CTS#-Pad4)") (class "Default")
      (node (ref "U$4") (pin "4") (pinfunction "CTS#_4") (pintype "bidirectional"))
    )
    (net (code "92") (name "unconnected-(U$4-RTS#-Pad16)") (class "Default")
      (node (ref "U$4") (pin "16") (pinfunction "RTS#_16") (pintype "bidirectional"))
    )
    (net (code "93") (name "unconnected-(U1B-PA8-Pad20)") (class "Default")
      (node (ref "U1") (pin "20") (pinfunction "PA8_20") (pintype "bidirectional"))
    )
    (net (code "94") (name "unconnected-(U1B-PA11-Pad23)") (class "Default")
      (node (ref "U1") (pin "23") (pinfunction "PA11_23") (pintype "bidirectional"))
    )
    (net (code "95") (name "unconnected-(U1B-PA12-Pad24)") (class "Default")
      (node (ref "U1") (pin "24") (pinfunction "PA12_24") (pintype "bidirectional"))
    )
    (net (code "96") (name "unconnected-(U1D-PB6-Pad33)") (class "Default")
      (node (ref "U1") (pin "33") (pinfunction "PB6_33") (pintype "bidirectional"))
    )
    (net (code "97") (name "unconnected-(U1D-PB7-Pad34)") (class "Default")
      (node (ref "U1") (pin "34") (pinfunction "PB7_34") (pintype "bidirectional"))
    )
    (net (code "98") (name "unconnected-(X2-PadID)") (class "Default")
      (node (ref "X2") (pin "ID") (pinfunction "ID_ID") (pintype "bidirectional"))
    )
  )
)
